# CpuMY.net
KiCad netlist of a schematic drawn in Altium Designer
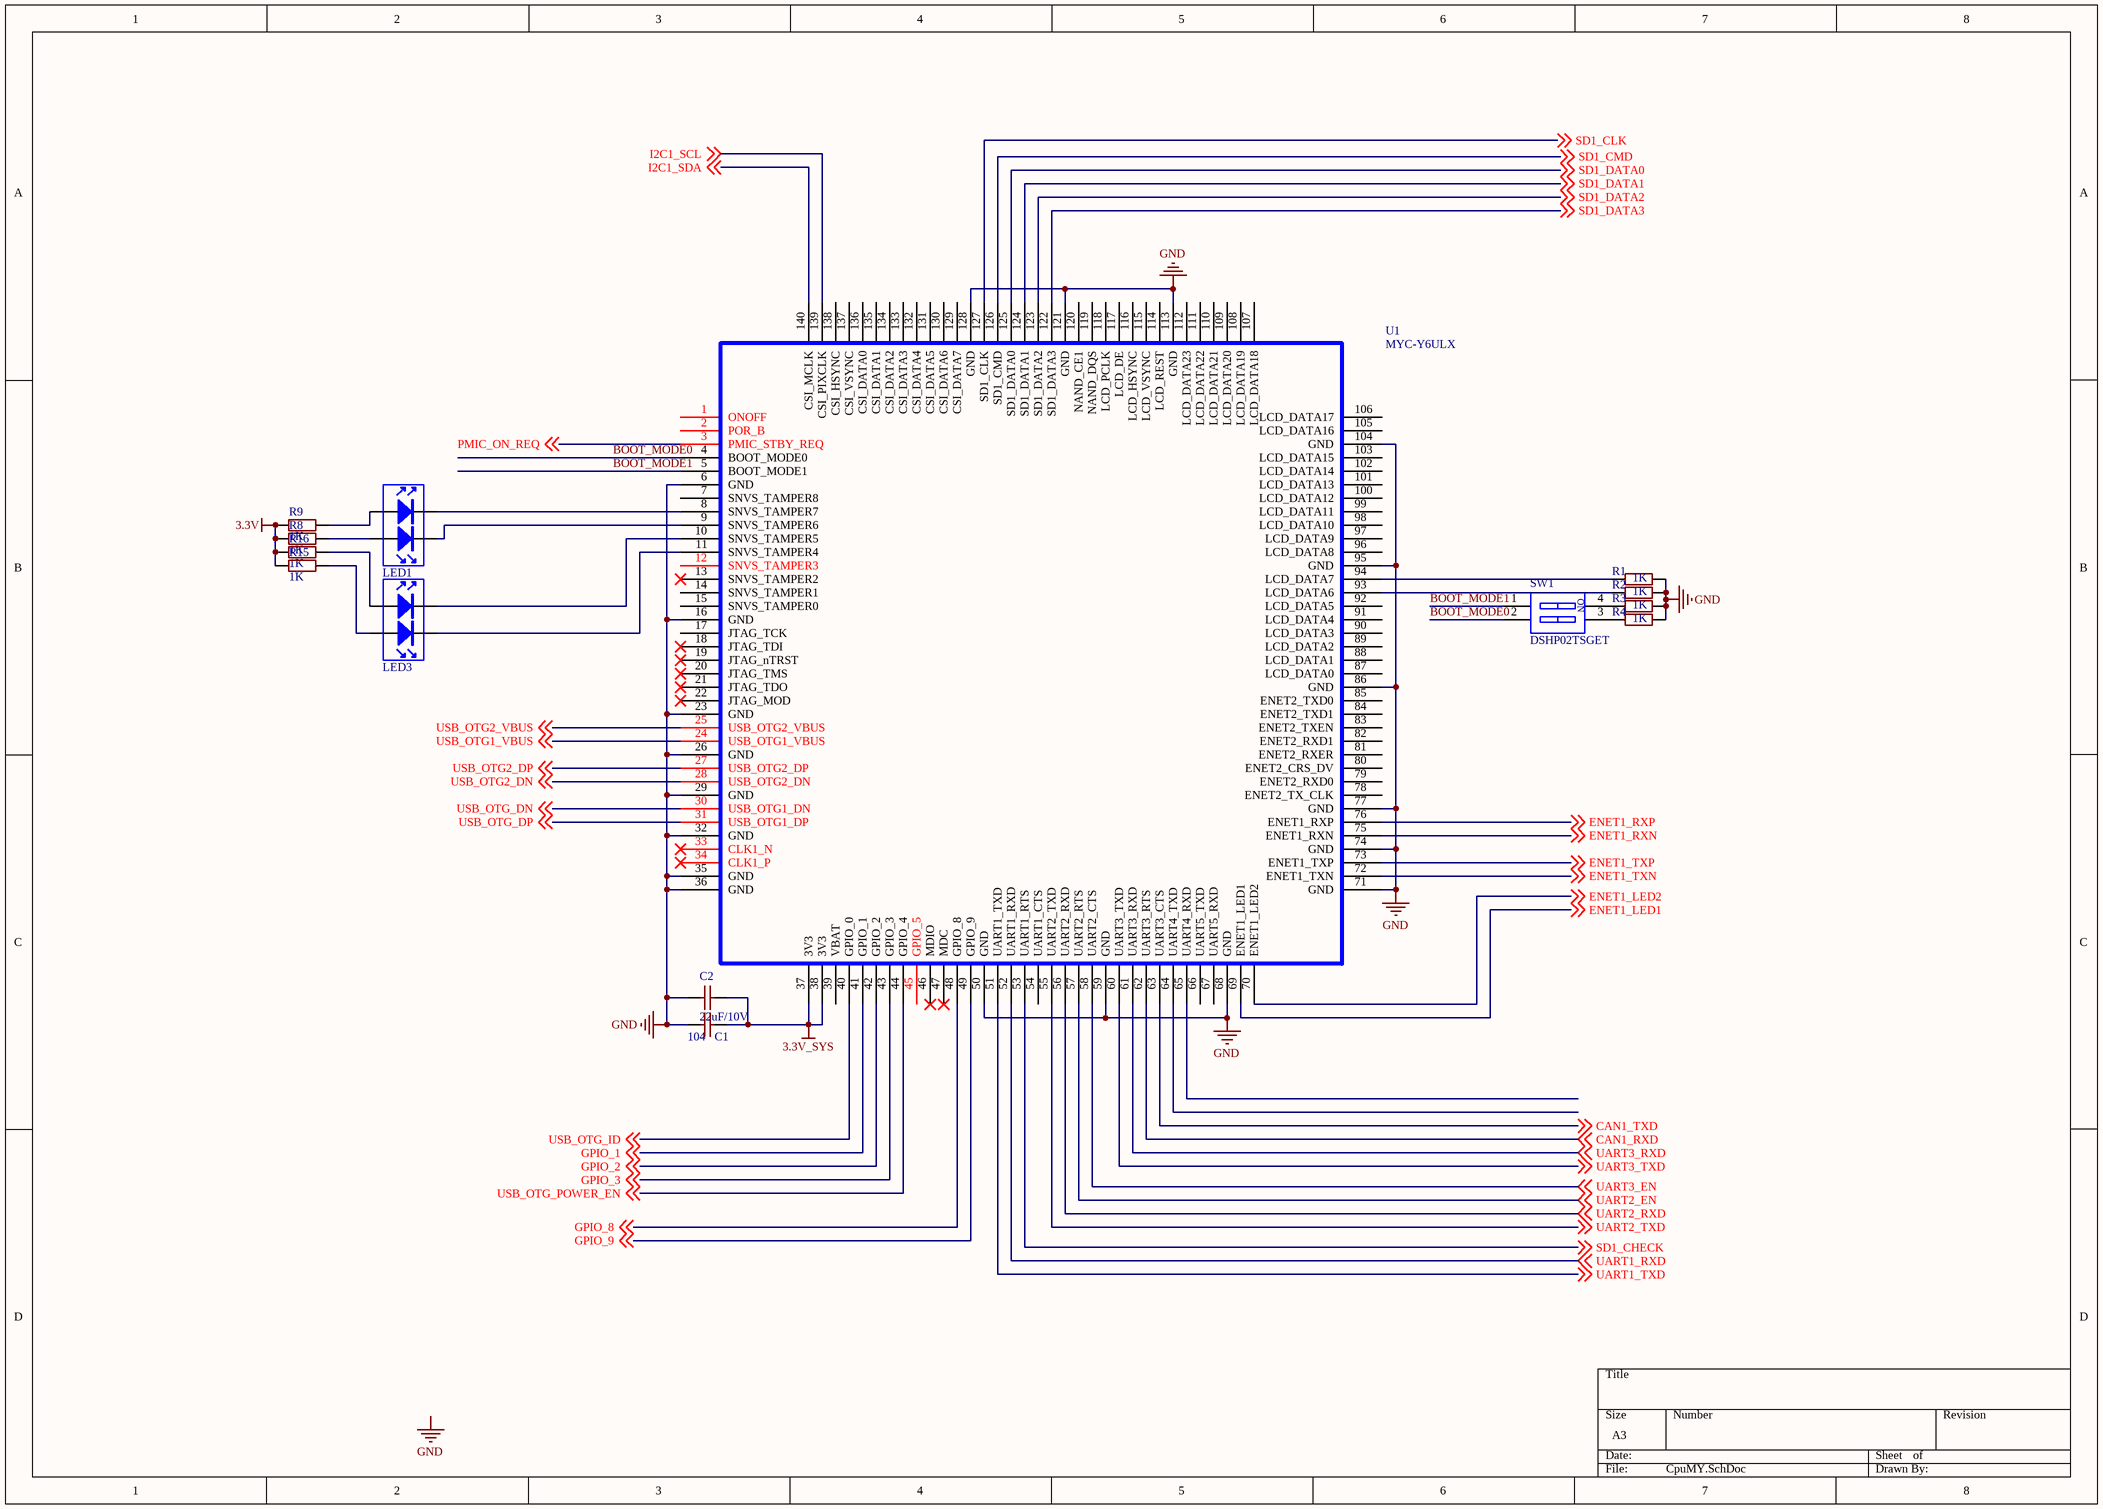
[diagram p0: CpuMY.SchDoc]

(export (version "E")
  (design (tool "Eeschema 10.0.6"))
  (components
    (comp (ref "C1")
      (value "104")
      (footprint "0805SMD_Cap")
      (description "贴片电容")
      (libsource (lib "ST_GND_Sch") (part "SMD_Cap"))
    )
    (comp (ref "C2")
      (value "22uF/10V")
      (footprint "0805SMD_Cap")
      (description "贴片电容")
      (libsource (lib "ST_GND_Sch") (part "SMD_Cap"))
    )
    (comp (ref "LED1")
      (value "LED_1")
      (footprint "DIP LED")
      (description "发光二极管")
      (libsource (lib "ST_GND_Sch") (part "LED_1"))
    )
    (comp (ref "LED3")
      (value "LED_1")
      (footprint "DIP LED")
      (description "发光二极管")
      (libsource (lib "ST_GND_Sch") (part "LED_1"))
    )
    (comp (ref "R1")
      (value "1K")
      (footprint "0805_SMD_R")
      (description "贴片电阻")
      (libsource (lib "ST_GND_Sch") (part "SMD_0805"))
    )
    (comp (ref "R2")
      (value "1K")
      (footprint "0805_SMD_R")
      (description "贴片电阻")
      (libsource (lib "ST_GND_Sch") (part "SMD_0805"))
    )
    (comp (ref "R3")
      (value "1K")
      (footprint "0805_SMD_R")
      (description "贴片电阻")
      (libsource (lib "ST_GND_Sch") (part "SMD_0805"))
    )
    (comp (ref "R4")
      (value "1K")
      (footprint "0805_SMD_R")
      (description "贴片电阻")
      (libsource (lib "ST_GND_Sch") (part "SMD_0805"))
    )
    (comp (ref "R8")
      (value "1K")
      (footprint "0805_SMD_R")
      (description "贴片电阻")
      (libsource (lib "ST_GND_Sch") (part "SMD_0805"))
    )
    (comp (ref "R9")
      (value "1K")
      (footprint "0805_SMD_R")
      (description "贴片电阻")
      (libsource (lib "ST_GND_Sch") (part "SMD_0805"))
    )
    (comp (ref "R15")
      (value "1K")
      (footprint "0805_SMD_R")
      (description "贴片电阻")
      (libsource (lib "") (part "SMD_0805_1"))
    )
    (comp (ref "R16")
      (value "1K")
      (footprint "0805_SMD_R")
      (description "贴片电阻")
      (libsource (lib "") (part "SMD_0805_1"))
    )
    (comp (ref "SW1")
      (value "DSHP02TSGET")
      (footprint "DSHP02TSGET")
      (libsource (lib "ST_GND_Sch") (part "拨码开关"))
    )
    (comp (ref "U1")
      (value "MYC-Y6ULX")
      (footprint "MYIMX6")
      (libsource (lib "ST_GND_Sch") (part "MYC-Y6ULX"))
    )
  )
  (nets
    (net (code "1") (name "/BOOT_MODE0") (class "Default")
      (node (ref "SW1") (pin "2") (pinfunction "A2_2") (pintype "passive"))
      (node (ref "U1") (pin "4") (pinfunction "BOOT_MODE0_4") (pintype "passive"))
    )
    (net (code "2") (name "/BOOT_MODE1") (class "Default")
      (node (ref "SW1") (pin "1") (pinfunction "A1_1") (pintype "passive"))
      (node (ref "U1") (pin "5") (pinfunction "BOOT_MODE1_5") (pintype "passive"))
    )
    (net (code "3") (name "3.3V") (class "Default")
      (node (ref "R15") (pin "2") (pinfunction "2_2") (pintype "passive"))
      (node (ref "R16") (pin "2") (pinfunction "2_2") (pintype "passive"))
      (node (ref "R8") (pin "1") (pinfunction "1_1") (pintype "passive"))
      (node (ref "R9") (pin "1") (pinfunction "1_1") (pintype "passive"))
    )
    (net (code "4") (name "3.3V_SYS") (class "Default")
      (node (ref "C1") (pin "2") (pintype "passive"))
      (node (ref "C2") (pin "1") (pintype "passive"))
      (node (ref "U1") (pin "37") (pinfunction "3V3_37") (pintype "passive"))
      (node (ref "U1") (pin "38") (pinfunction "3V3_38") (pintype "passive"))
    )
    (net (code "5") (name "CAN1_RXD") (class "Default")
      (node (ref "U1") (pin "62") (pinfunction "UART3_RTS_62") (pintype "passive"))
    )
    (net (code "6") (name "CAN1_TXD") (class "Default")
      (node (ref "U1") (pin "63") (pinfunction "UART3_CTS_63") (pintype "passive"))
    )
    (net (code "7") (name "ENET1_LED1") (class "Default")
      (node (ref "U1") (pin "69") (pinfunction "ENET1_LED1_69") (pintype "passive"))
    )
    (net (code "8") (name "ENET1_LED2") (class "Default")
      (node (ref "U1") (pin "70") (pinfunction "ENET1_LED2_70") (pintype "passive"))
    )
    (net (code "9") (name "ENET1_RXN") (class "Default")
      (node (ref "U1") (pin "75") (pinfunction "ENET1_RXN_75") (pintype "passive"))
    )
    (net (code "10") (name "ENET1_RXP") (class "Default")
      (node (ref "U1") (pin "76") (pinfunction "ENET1_RXP_76") (pintype "passive"))
    )
    (net (code "11") (name "ENET1_TXN") (class "Default")
      (node (ref "U1") (pin "72") (pinfunction "ENET1_TXN_72") (pintype "passive"))
    )
    (net (code "12") (name "ENET1_TXP") (class "Default")
      (node (ref "U1") (pin "73") (pinfunction "ENET1_TXP_73") (pintype "passive"))
    )
    (net (code "13") (name "GND") (class "Default")
      (node (ref "C1") (pin "1") (pintype "passive"))
      (node (ref "C2") (pin "2") (pintype "passive"))
      (node (ref "R1") (pin "2") (pinfunction "2_2") (pintype "passive"))
      (node (ref "R2") (pin "2") (pinfunction "2_2") (pintype "passive"))
      (node (ref "R3") (pin "2") (pinfunction "2_2") (pintype "passive"))
      (node (ref "R4") (pin "2") (pinfunction "2_2") (pintype "passive"))
      (node (ref "U1") (pin "104") (pinfunction "GND_104") (pintype "passive"))
      (node (ref "U1") (pin "113") (pinfunction "GND_113") (pintype "passive"))
      (node (ref "U1") (pin "121") (pinfunction "GND_121") (pintype "passive"))
      (node (ref "U1") (pin "128") (pinfunction "GND_128") (pintype "passive"))
      (node (ref "U1") (pin "16") (pinfunction "GND_16") (pintype "passive"))
      (node (ref "U1") (pin "23") (pinfunction "GND_23") (pintype "passive"))
      (node (ref "U1") (pin "26") (pinfunction "GND_26") (pintype "passive"))
      (node (ref "U1") (pin "29") (pinfunction "GND_29") (pintype "passive"))
      (node (ref "U1") (pin "32") (pinfunction "GND_32") (pintype "passive"))
      (node (ref "U1") (pin "35") (pinfunction "GND_35") (pintype "passive"))
      (node (ref "U1") (pin "36") (pinfunction "GND_36") (pintype "passive"))
      (node (ref "U1") (pin "50") (pinfunction "GND_50") (pintype "passive"))
      (node (ref "U1") (pin "59") (pinfunction "GND_59") (pintype "passive"))
      (node (ref "U1") (pin "6") (pinfunction "GND_6") (pintype "passive"))
      (node (ref "U1") (pin "68") (pinfunction "GND_68") (pintype "passive"))
      (node (ref "U1") (pin "71") (pinfunction "GND_71") (pintype "passive"))
      (node (ref "U1") (pin "74") (pinfunction "GND_74") (pintype "passive"))
      (node (ref "U1") (pin "77") (pinfunction "GND_77") (pintype "passive"))
      (node (ref "U1") (pin "86") (pinfunction "GND_86") (pintype "passive"))
      (node (ref "U1") (pin "95") (pinfunction "GND_95") (pintype "passive"))
    )
    (net (code "14") (name "GPIO_1") (class "Default")
      (node (ref "U1") (pin "41") (pinfunction "GPIO_1_41") (pintype "passive"))
    )
    (net (code "15") (name "GPIO_2") (class "Default")
      (node (ref "U1") (pin "42") (pinfunction "GPIO_2_42") (pintype "passive"))
    )
    (net (code "16") (name "GPIO_3") (class "Default")
      (node (ref "U1") (pin "43") (pinfunction "GPIO_3_43") (pintype "passive"))
    )
    (net (code "17") (name "GPIO_8") (class "Default")
      (node (ref "U1") (pin "48") (pinfunction "GPIO_8_48") (pintype "passive"))
    )
    (net (code "18") (name "GPIO_9") (class "Default")
      (node (ref "U1") (pin "49") (pinfunction "GPIO_9_49") (pintype "passive"))
    )
    (net (code "19") (name "I2C1_SCL") (class "Default")
      (node (ref "U1") (pin "139") (pinfunction "CSI_PIXCLK_139") (pintype "passive"))
    )
    (net (code "20") (name "I2C1_SDA") (class "Default")
      (node (ref "U1") (pin "140") (pinfunction "CSI_MCLK_140") (pintype "passive"))
    )
    (net (code "21") (name "Net-(LED1-Pad1)") (class "Default")
      (node (ref "LED1") (pin "1") (pintype "passive"))
      (node (ref "R9") (pin "2") (pinfunction "2_2") (pintype "passive"))
    )
    (net (code "22") (name "Net-(LED1-Pad3)") (class "Default")
      (node (ref "LED1") (pin "3") (pintype "passive"))
      (node (ref "R8") (pin "2") (pinfunction "2_2") (pintype "passive"))
    )
    (net (code "23") (name "Net-(LED3-Pad1)") (class "Default")
      (node (ref "LED3") (pin "1") (pintype "passive"))
      (node (ref "R16") (pin "1") (pinfunction "1_1") (pintype "passive"))
    )
    (net (code "24") (name "Net-(LED3-Pad3)") (class "Default")
      (node (ref "LED3") (pin "3") (pintype "passive"))
      (node (ref "R15") (pin "1") (pinfunction "1_1") (pintype "passive"))
    )
    (net (code "25") (name "Net-(SW1-B1)") (class "Default")
      (node (ref "R3") (pin "1") (pinfunction "1_1") (pintype "passive"))
      (node (ref "SW1") (pin "4") (pinfunction "B1_4") (pintype "passive"))
    )
    (net (code "26") (name "Net-(SW1-B2)") (class "Default")
      (node (ref "R4") (pin "1") (pinfunction "1_1") (pintype "passive"))
      (node (ref "SW1") (pin "3") (pinfunction "B2_3") (pintype "passive"))
    )
    (net (code "27") (name "Net-(U1-LCD_DATA6)") (class "Default")
      (node (ref "R2") (pin "1") (pinfunction "1_1") (pintype "passive"))
      (node (ref "U1") (pin "93") (pinfunction "LCD_DATA6_93") (pintype "passive"))
    )
    (net (code "28") (name "Net-(U1-LCD_DATA7)") (class "Default")
      (node (ref "R1") (pin "1") (pinfunction "1_1") (pintype "passive"))
      (node (ref "U1") (pin "94") (pinfunction "LCD_DATA7_94") (pintype "passive"))
    )
    (net (code "29") (name "Net-(U1-SNVS_TAMPER4)") (class "Default")
      (node (ref "LED3") (pin "4") (pintype "passive"))
      (node (ref "U1") (pin "11") (pinfunction "SNVS_TAMPER4_11") (pintype "passive"))
    )
    (net (code "30") (name "Net-(U1-SNVS_TAMPER5)") (class "Default")
      (node (ref "LED3") (pin "2") (pintype "passive"))
      (node (ref "U1") (pin "10") (pinfunction "SNVS_TAMPER5_10") (pintype "passive"))
    )
    (net (code "31") (name "Net-(U1-SNVS_TAMPER6)") (class "Default")
      (node (ref "LED1") (pin "4") (pintype "passive"))
      (node (ref "U1") (pin "9") (pinfunction "SNVS_TAMPER6_9") (pintype "passive"))
    )
    (net (code "32") (name "Net-(U1-SNVS_TAMPER7)") (class "Default")
      (node (ref "LED1") (pin "2") (pintype "passive"))
      (node (ref "U1") (pin "8") (pinfunction "SNVS_TAMPER7_8") (pintype "passive"))
    )
    (net (code "33") (name "PMIC_ON_REQ") (class "Default")
      (node (ref "U1") (pin "3") (pinfunction "PMIC_STBY_REQ_3") (pintype "passive"))
    )
    (net (code "34") (name "SD1_CHECK") (class "Default")
      (node (ref "U1") (pin "53") (pinfunction "UART1_RTS_53") (pintype "passive"))
    )
    (net (code "35") (name "SD1_CLK") (class "Default")
      (node (ref "U1") (pin "127") (pinfunction "SD1_CLK_127") (pintype "passive"))
    )
    (net (code "36") (name "SD1_CMD") (class "Default")
      (node (ref "U1") (pin "126") (pinfunction "SD1_CMD_126") (pintype "passive"))
    )
    (net (code "37") (name "SD1_DATA0") (class "Default")
      (node (ref "U1") (pin "125") (pinfunction "SD1_DATA0_125") (pintype "passive"))
    )
    (net (code "38") (name "SD1_DATA1") (class "Default")
      (node (ref "U1") (pin "124") (pinfunction "SD1_DATA1_124") (pintype "passive"))
    )
    (net (code "39") (name "SD1_DATA2") (class "Default")
      (node (ref "U1") (pin "123") (pinfunction "SD1_DATA2_123") (pintype "passive"))
    )
    (net (code "40") (name "SD1_DATA3") (class "Default")
      (node (ref "U1") (pin "122") (pinfunction "SD1_DATA3_122") (pintype "passive"))
    )
    (net (code "41") (name "UART1_RXD") (class "Default")
      (node (ref "U1") (pin "52") (pinfunction "UART1_RXD_52") (pintype "passive"))
    )
    (net (code "42") (name "UART1_TXD") (class "Default")
      (node (ref "U1") (pin "51") (pinfunction "UART1_TXD_51") (pintype "passive"))
    )
    (net (code "43") (name "UART2_EN") (class "Default")
      (node (ref "U1") (pin "57") (pinfunction "UART2_RTS_57") (pintype "passive"))
    )
    (net (code "44") (name "UART2_RXD") (class "Default")
      (node (ref "U1") (pin "56") (pinfunction "UART2_RXD_56") (pintype "passive"))
    )
    (net (code "45") (name "UART2_TXD") (class "Default")
      (node (ref "U1") (pin "55") (pinfunction "UART2_TXD_55") (pintype "passive"))
    )
    (net (code "46") (name "UART3_EN") (class "Default")
      (node (ref "U1") (pin "58") (pinfunction "UART2_CTS_58") (pintype "passive"))
    )
    (net (code "47") (name "UART3_RXD") (class "Default")
      (node (ref "U1") (pin "61") (pinfunction "UART3_RXD_61") (pintype "passive"))
    )
    (net (code "48") (name "UART3_TXD") (class "Default")
      (node (ref "U1") (pin "60") (pinfunction "UART3_TXD_60") (pintype "passive"))
    )
    (net (code "49") (name "USB_OTG1_VBUS") (class "Default")
      (node (ref "U1") (pin "24") (pinfunction "USB_OTG1_VBUS_24") (pintype "passive"))
    )
    (net (code "50") (name "USB_OTG2_DN") (class "Default")
      (node (ref "U1") (pin "28") (pinfunction "USB_OTG2_DN_28") (pintype "passive"))
    )
    (net (code "51") (name "USB_OTG2_DP") (class "Default")
      (node (ref "U1") (pin "27") (pinfunction "USB_OTG2_DP_27") (pintype "passive"))
    )
    (net (code "52") (name "USB_OTG2_VBUS") (class "Default")
      (node (ref "U1") (pin "25") (pinfunction "USB_OTG2_VBUS_25") (pintype "passive"))
    )
    (net (code "53") (name "USB_OTG_DN") (class "Default")
      (node (ref "U1") (pin "30") (pinfunction "USB_OTG1_DN_30") (pintype "passive"))
    )
    (net (code "54") (name "USB_OTG_DP") (class "Default")
      (node (ref "U1") (pin "31") (pinfunction "USB_OTG1_DP_31") (pintype "passive"))
    )
    (net (code "55") (name "USB_OTG_ID") (class "Default")
      (node (ref "U1") (pin "40") (pinfunction "GPIO_0_40") (pintype "passive"))
    )
    (net (code "56") (name "USB_OTG_POWER_EN") (class "Default")
      (node (ref "U1") (pin "44") (pinfunction "GPIO_4_44") (pintype "passive"))
    )
    (net (code "57") (name "unconnected-(U1-CLK1_N-Pad33)") (class "Default")
      (node (ref "U1") (pin "33") (pinfunction "CLK1_N_33") (pintype "passive+no_connect"))
    )
    (net (code "58") (name "unconnected-(U1-CLK1_P-Pad34)") (class "Default")
      (node (ref "U1") (pin "34") (pinfunction "CLK1_P_34") (pintype "passive+no_connect"))
    )
    (net (code "59") (name "unconnected-(U1-CSI_DATA0-Pad136)") (class "Default")
      (node (ref "U1") (pin "136") (pinfunction "CSI_DATA0_136") (pintype "passive"))
    )
    (net (code "60") (name "unconnected-(U1-CSI_DATA1-Pad135)") (class "Default")
      (node (ref "U1") (pin "135") (pinfunction "CSI_DATA1_135") (pintype "passive"))
    )
    (net (code "61") (name "unconnected-(U1-CSI_DATA2-Pad134)") (class "Default")
      (node (ref "U1") (pin "134") (pinfunction "CSI_DATA2_134") (pintype "passive"))
    )
    (net (code "62") (name "unconnected-(U1-CSI_DATA3-Pad133)") (class "Default")
      (node (ref "U1") (pin "133") (pinfunction "CSI_DATA3_133") (pintype "passive"))
    )
    (net (code "63") (name "unconnected-(U1-CSI_DATA4-Pad132)") (class "Default")
      (node (ref "U1") (pin "132") (pinfunction "CSI_DATA4_132") (pintype "passive"))
    )
    (net (code "64") (name "unconnected-(U1-CSI_DATA5-Pad131)") (class "Default")
      (node (ref "U1") (pin "131") (pinfunction "CSI_DATA5_131") (pintype "passive"))
    )
    (net (code "65") (name "unconnected-(U1-CSI_DATA6-Pad130)") (class "Default")
      (node (ref "U1") (pin "130") (pinfunction "CSI_DATA6_130") (pintype "passive"))
    )
    (net (code "66") (name "unconnected-(U1-CSI_DATA7-Pad129)") (class "Default")
      (node (ref "U1") (pin "129") (pinfunction "CSI_DATA7_129") (pintype "passive"))
    )
    (net (code "67") (name "unconnected-(U1-CSI_HSYNC-Pad138)") (class "Default")
      (node (ref "U1") (pin "138") (pinfunction "CSI_HSYNC_138") (pintype "passive"))
    )
    (net (code "68") (name "unconnected-(U1-CSI_VSYNC-Pad137)") (class "Default")
      (node (ref "U1") (pin "137") (pinfunction "CSI_VSYNC_137") (pintype "passive"))
    )
    (net (code "69") (name "unconnected-(U1-ENET2_CRS_DV-Pad80)") (class "Default")
      (node (ref "U1") (pin "80") (pinfunction "ENET2_CRS_DV_80") (pintype "passive"))
    )
    (net (code "70") (name "unconnected-(U1-ENET2_RXD0-Pad79)") (class "Default")
      (node (ref "U1") (pin "79") (pinfunction "ENET2_RXD0_79") (pintype "passive"))
    )
    (net (code "71") (name "unconnected-(U1-ENET2_RXD1-Pad82)") (class "Default")
      (node (ref "U1") (pin "82") (pinfunction "ENET2_RXD1_82") (pintype "passive"))
    )
    (net (code "72") (name "unconnected-(U1-ENET2_RXER-Pad81)") (class "Default")
      (node (ref "U1") (pin "81") (pinfunction "ENET2_RXER_81") (pintype "passive"))
    )
    (net (code "73") (name "unconnected-(U1-ENET2_TXD0-Pad85)") (class "Default")
      (node (ref "U1") (pin "85") (pinfunction "ENET2_TXD0_85") (pintype "passive"))
    )
    (net (code "74") (name "unconnected-(U1-ENET2_TXD1-Pad84)") (class "Default")
      (node (ref "U1") (pin "84") (pinfunction "ENET2_TXD1_84") (pintype "passive"))
    )
    (net (code "75") (name "unconnected-(U1-ENET2_TXEN-Pad83)") (class "Default")
      (node (ref "U1") (pin "83") (pinfunction "ENET2_TXEN_83") (pintype "passive"))
    )
    (net (code "76") (name "unconnected-(U1-ENET2_TX_CLK-Pad78)") (class "Default")
      (node (ref "U1") (pin "78") (pinfunction "ENET2_TX_CLK_78") (pintype "passive"))
    )
    (net (code "77") (name "unconnected-(U1-GPIO_5-Pad45)") (class "Default")
      (node (ref "U1") (pin "45") (pinfunction "GPIO_5_45") (pintype "passive"))
    )
    (net (code "78") (name "unconnected-(U1-JTAG_MOD-Pad22)") (class "Default")
      (node (ref "U1") (pin "22") (pinfunction "JTAG_MOD_22") (pintype "passive+no_connect"))
    )
    (net (code "79") (name "unconnected-(U1-JTAG_TCK-Pad17)") (class "Default")
      (node (ref "U1") (pin "17") (pinfunction "JTAG_TCK_17") (pintype "passive"))
    )
    (net (code "80") (name "unconnected-(U1-JTAG_TDI-Pad18)") (class "Default")
      (node (ref "U1") (pin "18") (pinfunction "JTAG_TDI_18") (pintype "passive+no_connect"))
    )
    (net (code "81") (name "unconnected-(U1-JTAG_TDO-Pad21)") (class "Default")
      (node (ref "U1") (pin "21") (pinfunction "JTAG_TDO_21") (pintype "passive+no_connect"))
    )
    (net (code "82") (name "unconnected-(U1-JTAG_TMS-Pad20)") (class "Default")
      (node (ref "U1") (pin "20") (pinfunction "JTAG_TMS_20") (pintype "passive+no_connect"))
    )
    (net (code "83") (name "unconnected-(U1-JTAG_nTRST-Pad19)") (class "Default")
      (node (ref "U1") (pin "19") (pinfunction "JTAG_nTRST_19") (pintype "passive+no_connect"))
    )
    (net (code "84") (name "unconnected-(U1-LCD_DATA0-Pad87)") (class "Default")
      (node (ref "U1") (pin "87") (pinfunction "LCD_DATA0_87") (pintype "passive"))
    )
    (net (code "85") (name "unconnected-(U1-LCD_DATA1-Pad88)") (class "Default")
      (node (ref "U1") (pin "88") (pinfunction "LCD_DATA1_88") (pintype "passive"))
    )
    (net (code "86") (name "unconnected-(U1-LCD_DATA2-Pad89)") (class "Default")
      (node (ref "U1") (pin "89") (pinfunction "LCD_DATA2_89") (pintype "passive"))
    )
    (net (code "87") (name "unconnected-(U1-LCD_DATA3-Pad90)") (class "Default")
      (node (ref "U1") (pin "90") (pinfunction "LCD_DATA3_90") (pintype "passive"))
    )
    (net (code "88") (name "unconnected-(U1-LCD_DATA4-Pad91)") (class "Default")
      (node (ref "U1") (pin "91") (pinfunction "LCD_DATA4_91") (pintype "passive"))
    )
    (net (code "89") (name "unconnected-(U1-LCD_DATA5-Pad92)") (class "Default")
      (node (ref "U1") (pin "92") (pinfunction "LCD_DATA5_92") (pintype "passive"))
    )
    (net (code "90") (name "unconnected-(U1-LCD_DATA8-Pad96)") (class "Default")
      (node (ref "U1") (pin "96") (pinfunction "LCD_DATA8_96") (pintype "passive"))
    )
    (net (code "91") (name "unconnected-(U1-LCD_DATA9-Pad97)") (class "Default")
      (node (ref "U1") (pin "97") (pinfunction "LCD_DATA9_97") (pintype "passive"))
    )
    (net (code "92") (name "unconnected-(U1-LCD_DATA10-Pad98)") (class "Default")
      (node (ref "U1") (pin "98") (pinfunction "LCD_DATA10_98") (pintype "passive"))
    )
    (net (code "93") (name "unconnected-(U1-LCD_DATA11-Pad99)") (class "Default")
      (node (ref "U1") (pin "99") (pinfunction "LCD_DATA11_99") (pintype "passive"))
    )
    (net (code "94") (name "unconnected-(U1-LCD_DATA12-Pad100)") (class "Default")
      (node (ref "U1") (pin "100") (pinfunction "LCD_DATA12_100") (pintype "passive"))
    )
    (net (code "95") (name "unconnected-(U1-LCD_DATA13-Pad101)") (class "Default")
      (node (ref "U1") (pin "101") (pinfunction "LCD_DATA13_101") (pintype "passive"))
    )
    (net (code "96") (name "unconnected-(U1-LCD_DATA14-Pad102)") (class "Default")
      (node (ref "U1") (pin "102") (pinfunction "LCD_DATA14_102") (pintype "passive"))
    )
    (net (code "97") (name "unconnected-(U1-LCD_DATA15-Pad103)") (class "Default")
      (node (ref "U1") (pin "103") (pinfunction "LCD_DATA15_103") (pintype "passive"))
    )
    (net (code "98") (name "unconnected-(U1-LCD_DATA16-Pad105)") (class "Default")
      (node (ref "U1") (pin "105") (pinfunction "LCD_DATA16_105") (pintype "passive"))
    )
    (net (code "99") (name "unconnected-(U1-LCD_DATA17-Pad106)") (class "Default")
      (node (ref "U1") (pin "106") (pinfunction "LCD_DATA17_106") (pintype "passive"))
    )
    (net (code "100") (name "unconnected-(U1-LCD_DATA18-Pad107)") (class "Default")
      (node (ref "U1") (pin "107") (pinfunction "LCD_DATA18_107") (pintype "passive"))
    )
    (net (code "101") (name "unconnected-(U1-LCD_DATA19-Pad108)") (class "Default")
      (node (ref "U1") (pin "108") (pinfunction "LCD_DATA19_108") (pintype "passive"))
    )
    (net (code "102") (name "unconnected-(U1-LCD_DATA20-Pad109)") (class "Default")
      (node (ref "U1") (pin "109") (pinfunction "LCD_DATA20_109") (pintype "passive"))
    )
    (net (code "103") (name "unconnected-(U1-LCD_DATA21-Pad110)") (class "Default")
      (node (ref "U1") (pin "110") (pinfunction "LCD_DATA21_110") (pintype "passive"))
    )
    (net (code "104") (name "unconnected-(U1-LCD_DATA22-Pad111)") (class "Default")
      (node (ref "U1") (pin "111") (pinfunction "LCD_DATA22_111") (pintype "passive"))
    )
    (net (code "105") (name "unconnected-(U1-LCD_DATA23-Pad112)") (class "Default")
      (node (ref "U1") (pin "112") (pinfunction "LCD_DATA23_112") (pintype "passive"))
    )
    (net (code "106") (name "unconnected-(U1-LCD_DE-Pad117)") (class "Default")
      (node (ref "U1") (pin "117") (pinfunction "LCD_DE_117") (pintype "passive"))
    )
    (net (code "107") (name "unconnected-(U1-LCD_HSYNC-Pad116)") (class "Default")
      (node (ref "U1") (pin "116") (pinfunction "LCD_HSYNC_116") (pintype "passive"))
    )
    (net (code "108") (name "unconnected-(U1-LCD_PCLK-Pad118)") (class "Default")
      (node (ref "U1") (pin "118") (pinfunction "LCD_PCLK_118") (pintype "passive"))
    )
    (net (code "109") (name "unconnected-(U1-LCD_REST-Pad114)") (class "Default")
      (node (ref "U1") (pin "114") (pinfunction "LCD_REST_114") (pintype "passive"))
    )
    (net (code "110") (name "unconnected-(U1-LCD_VSYNC-Pad115)") (class "Default")
      (node (ref "U1") (pin "115") (pinfunction "LCD_VSYNC_115") (pintype "passive"))
    )
    (net (code "111") (name "unconnected-(U1-MDC-Pad47)") (class "Default")
      (node (ref "U1") (pin "47") (pinfunction "MDC_47") (pintype "passive+no_connect"))
    )
    (net (code "112") (name "unconnected-(U1-MDIO-Pad46)") (class "Default")
      (node (ref "U1") (pin "46") (pinfunction "MDIO_46") (pintype "passive+no_connect"))
    )
    (net (code "113") (name "unconnected-(U1-NAND_CE1-Pad120)") (class "Default")
      (node (ref "U1") (pin "120") (pinfunction "NAND_CE1_120") (pintype "passive"))
    )
    (net (code "114") (name "unconnected-(U1-NAND_DQS-Pad119)") (class "Default")
      (node (ref "U1") (pin "119") (pinfunction "NAND_DQS_119") (pintype "passive"))
    )
    (net (code "115") (name "unconnected-(U1-ONOFF-Pad1)") (class "Default")
      (node (ref "U1") (pin "1") (pinfunction "ONOFF_1") (pintype "passive"))
    )
    (net (code "116") (name "unconnected-(U1-POR_B-Pad2)") (class "Default")
      (node (ref "U1") (pin "2") (pinfunction "POR_B_2") (pintype "passive"))
    )
    (net (code "117") (name "unconnected-(U1-SNVS_TAMPER0-Pad15)") (class "Default")
      (node (ref "U1") (pin "15") (pinfunction "SNVS_TAMPER0_15") (pintype "passive"))
    )
    (net (code "118") (name "unconnected-(U1-SNVS_TAMPER1-Pad14)") (class "Default")
      (node (ref "U1") (pin "14") (pinfunction "SNVS_TAMPER1_14") (pintype "passive"))
    )
    (net (code "119") (name "unconnected-(U1-SNVS_TAMPER2-Pad13)") (class "Default")
      (node (ref "U1") (pin "13") (pinfunction "SNVS_TAMPER2_13") (pintype "passive+no_connect"))
    )
    (net (code "120") (name "unconnected-(U1-SNVS_TAMPER3-Pad12)") (class "Default")
      (node (ref "U1") (pin "12") (pinfunction "SNVS_TAMPER3_12") (pintype "passive"))
    )
    (net (code "121") (name "unconnected-(U1-SNVS_TAMPER8-Pad7)") (class "Default")
      (node (ref "U1") (pin "7") (pinfunction "SNVS_TAMPER8_7") (pintype "passive"))
    )
    (net (code "122") (name "unconnected-(U1-UART1_CTS-Pad54)") (class "Default")
      (node (ref "U1") (pin "54") (pinfunction "UART1_CTS_54") (pintype "passive"))
    )
    (net (code "123") (name "unconnected-(U1-UART4_RXD-Pad65)") (class "Default")
      (node (ref "U1") (pin "65") (pinfunction "UART4_RXD_65") (pintype "passive"))
    )
    (net (code "124") (name "unconnected-(U1-UART4_TXD-Pad64)") (class "Default")
      (node (ref "U1") (pin "64") (pinfunction "UART4_TXD_64") (pintype "passive"))
    )
    (net (code "125") (name "unconnected-(U1-UART5_RXD-Pad67)") (class "Default")
      (node (ref "U1") (pin "67") (pinfunction "UART5_RXD_67") (pintype "passive"))
    )
    (net (code "126") (name "unconnected-(U1-UART5_TXD-Pad66)") (class "Default")
      (node (ref "U1") (pin "66") (pinfunction "UART5_TXD_66") (pintype "passive"))
    )
    (net (code "127") (name "unconnected-(U1-VBAT-Pad39)") (class "Default")
      (node (ref "U1") (pin "39") (pinfunction "VBAT_39") (pintype "passive"))
    )
  )
)
